# DRIVER_5V.net
KiCad netlist of a schematic drawn in EAGLE
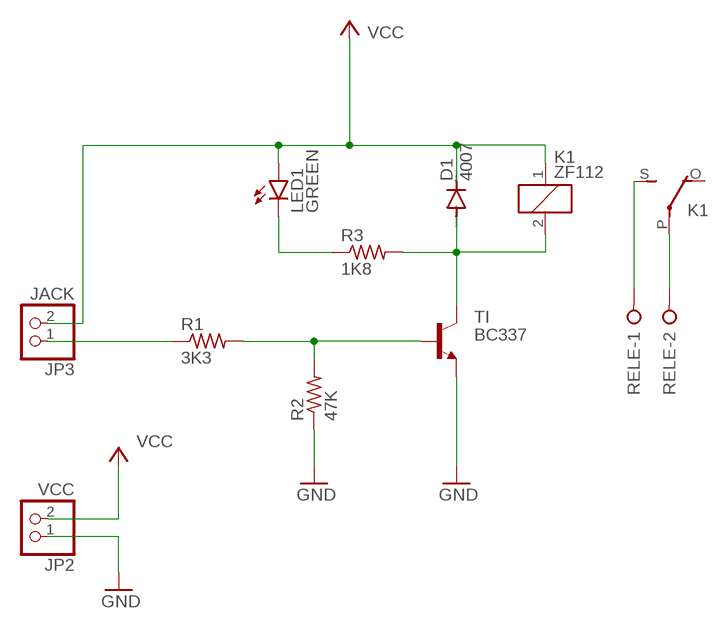
[diagram p0: schematic, sheet 1]

(export (version "E")
  (design (tool "Eeschema 10.0.6"))
  (components
    (comp (ref "D1")
      (value "4007")
      (footprint "eagle-import:DO35-10")
      (libsource (lib "eagle-import") (part "1N4148DO35-10"))
    )
    (comp (ref "JP2")
      (value "VCC")
      (footprint "eagle-import:1X02")
      (libsource (lib "eagle-import") (part "PINHD-1X2"))
    )
    (comp (ref "JP3")
      (value "JACK")
      (footprint "eagle-import:1X02")
      (libsource (lib "eagle-import") (part "PINHD-1X2"))
    )
    (comp (ref "K1")
      (value "ZF112")
      (footprint "eagle-import:ZF112")
      (libsource (lib "eagle-import") (part "ZF112"))
    )
    (comp (ref "LED1")
      (value "GREEN")
      (footprint "eagle-import:LED5MM")
      (libsource (lib "eagle-import") (part "LED5MM"))
    )
    (comp (ref "R1")
      (value "3K3")
      (footprint "eagle-import:0207_10")
      (libsource (lib "eagle-import") (part "R-US_0207/10"))
    )
    (comp (ref "R2")
      (value "47K")
      (footprint "eagle-import:0207_10")
      (libsource (lib "eagle-import") (part "R-US_0207/10"))
    )
    (comp (ref "R3")
      (value "1K8")
      (footprint "eagle-import:0207_10")
      (libsource (lib "eagle-import") (part "R-US_0207/10"))
    )
    (comp (ref "RELE")
      (value "W237-02P")
      (footprint "eagle-import:W237-132")
      (libsource (lib "eagle-import") (part "W237-02P"))
    )
    (comp (ref "TI")
      (value "BC337")
      (footprint "eagle-import:TO92-CBE")
      (libsource (lib "eagle-import") (part "-NPN-TO92-CBE2N4124"))
    )
  )
  (nets
    (net (code "1") (name "GND") (class "Default")
      (node (ref "JP2") (pin "1") (pinfunction "1_1") (pintype "passive"))
      (node (ref "R2") (pin "1") (pinfunction "1_1") (pintype "passive"))
      (node (ref "TI") (pin "E") (pinfunction "E_E") (pintype "passive"))
    )
    (net (code "2") (name "Net-(D1-PadA)") (class "Default")
      (node (ref "D1") (pin "A") (pinfunction "A_A") (pintype "passive"))
      (node (ref "K1") (pin "2") (pinfunction "2_2") (pintype "passive"))
      (node (ref "R3") (pin "2") (pinfunction "2_2") (pintype "passive"))
      (node (ref "TI") (pin "C") (pinfunction "C_C") (pintype "passive"))
    )
    (net (code "3") (name "Net-(JP3-Pad1)") (class "Default")
      (node (ref "JP3") (pin "1") (pinfunction "1_1") (pintype "passive"))
      (node (ref "R1") (pin "1") (pinfunction "1_1") (pintype "passive"))
    )
    (net (code "4") (name "Net-(LED1-C)") (class "Default")
      (node (ref "LED1") (pin "K") (pinfunction "C_K") (pintype "passive"))
      (node (ref "R3") (pin "1") (pinfunction "1_1") (pintype "passive"))
    )
    (net (code "5") (name "Net-(R1-Pad2)") (class "Default")
      (node (ref "R1") (pin "2") (pinfunction "2_2") (pintype "passive"))
      (node (ref "R2") (pin "2") (pinfunction "2_2") (pintype "passive"))
      (node (ref "TI") (pin "B") (pinfunction "B_B") (pintype "passive"))
    )
    (net (code "6") (name "Net-(RELEA-KL)") (class "Default")
      (node (ref "K1") (pin "S") (pinfunction "S_S") (pintype "passive"))
      (node (ref "RELE") (pin "1") (pinfunction "KL_1") (pintype "passive"))
    )
    (net (code "7") (name "Net-(RELEB-KL)") (class "Default")
      (node (ref "K1") (pin "P") (pinfunction "P_P") (pintype "passive"))
      (node (ref "RELE") (pin "2") (pinfunction "KL_2") (pintype "passive"))
    )
    (net (code "8") (name "VCC") (class "Default")
      (node (ref "D1") (pin "C") (pinfunction "C_C") (pintype "passive"))
      (node (ref "JP2") (pin "2") (pinfunction "2_2") (pintype "passive"))
      (node (ref "JP3") (pin "2") (pinfunction "2_2") (pintype "passive"))
      (node (ref "K1") (pin "1") (pinfunction "1_1") (pintype "passive"))
      (node (ref "LED1") (pin "A") (pinfunction "A_A") (pintype "passive"))
    )
    (net (code "9") (name "unconnected-(K1-PadO)") (class "Default")
      (node (ref "K1") (pin "O") (pinfunction "O_O") (pintype "passive"))
    )
  )
)
